# 5VACDC.net
KiCad netlist of a schematic drawn in EAGLE
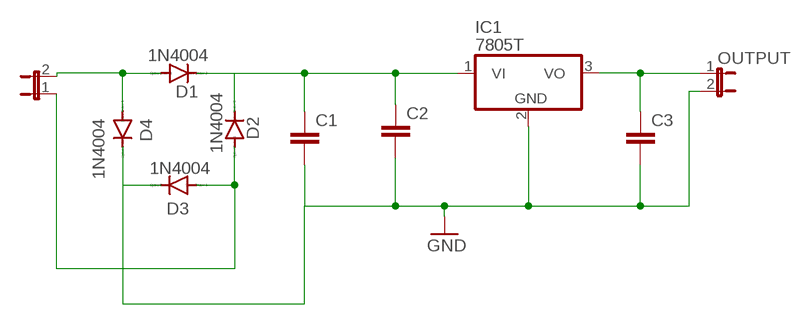
[diagram p0: schematic, sheet 1]

(export (version "E")
  (design (tool "Eeschema 10.0.6"))
  (components
    (comp (ref "C1")
      (value "C2,5-3")
      (footprint "eagle-import:C2.5-3")
      (libsource (lib "eagle-import") (part "C2,5-3"))
    )
    (comp (ref "C2")
      (value "C2,5-3")
      (footprint "eagle-import:C2.5-3")
      (libsource (lib "eagle-import") (part "C2,5-3"))
    )
    (comp (ref "C3")
      (value "C2,5-3")
      (footprint "eagle-import:C2.5-3")
      (libsource (lib "eagle-import") (part "C2,5-3"))
    )
    (comp (ref "D1")
      (value "1N4004")
      (footprint "eagle-import:DO41-10")
      (libsource (lib "eagle-import") (part "1N4004"))
    )
    (comp (ref "D2")
      (value "1N4004")
      (footprint "eagle-import:DO41-10")
      (libsource (lib "eagle-import") (part "1N4004"))
    )
    (comp (ref "D3")
      (value "1N4004")
      (footprint "eagle-import:DO41-10")
      (libsource (lib "eagle-import") (part "1N4004"))
    )
    (comp (ref "D4")
      (value "1N4004")
      (footprint "eagle-import:DO41-10")
      (libsource (lib "eagle-import") (part "1N4004"))
    )
    (comp (ref "IC1")
      (value "7805T")
      (footprint "eagle-import:TO220H")
      (libsource (lib "eagle-import") (part "78T05"))
    )
    (comp (ref "INPUT")
      (value "JP1E")
      (footprint "eagle-import:JP1")
      (libsource (lib "eagle-import") (part "JP1E"))
    )
    (comp (ref "OUTPUT")
      (value "JP1E")
      (footprint "eagle-import:JP1")
      (libsource (lib "eagle-import") (part "JP1E"))
    )
  )
  (nets
    (net (code "1") (name "GND") (class "Default")
      (node (ref "C1") (pin "2") (pinfunction "2_2") (pintype "passive"))
      (node (ref "C2") (pin "2") (pinfunction "2_2") (pintype "passive"))
      (node (ref "C3") (pin "2") (pinfunction "2_2") (pintype "passive"))
      (node (ref "D3") (pin "C") (pinfunction "C_C") (pintype "passive"))
      (node (ref "D4") (pin "C") (pinfunction "C_C") (pintype "passive"))
      (node (ref "IC1") (pin "2") (pinfunction "GND_2") (pintype "passive"))
      (node (ref "OUTPUT") (pin "2") (pinfunction "2_2") (pintype "passive"))
    )
    (net (code "2") (name "Net-(D1-PadA)") (class "Default")
      (node (ref "D1") (pin "A") (pinfunction "A_A") (pintype "passive"))
      (node (ref "D4") (pin "A") (pinfunction "A_A") (pintype "passive"))
      (node (ref "INPUT") (pin "2") (pinfunction "2_2") (pintype "passive"))
    )
    (net (code "3") (name "Net-(D2-PadA)") (class "Default")
      (node (ref "D2") (pin "A") (pinfunction "A_A") (pintype "passive"))
      (node (ref "D3") (pin "A") (pinfunction "A_A") (pintype "passive"))
      (node (ref "INPUT") (pin "1") (pinfunction "1_1") (pintype "passive"))
    )
    (net (code "4") (name "Net-(IC1-VI)") (class "Default")
      (node (ref "C1") (pin "1") (pinfunction "1_1") (pintype "passive"))
      (node (ref "C2") (pin "1") (pinfunction "1_1") (pintype "passive"))
      (node (ref "D1") (pin "C") (pinfunction "C_C") (pintype "passive"))
      (node (ref "D2") (pin "C") (pinfunction "C_C") (pintype "passive"))
      (node (ref "IC1") (pin "1") (pinfunction "VI_1") (pintype "input"))
    )
    (net (code "5") (name "Net-(IC1-VO)") (class "Default")
      (node (ref "C3") (pin "1") (pinfunction "1_1") (pintype "passive"))
      (node (ref "IC1") (pin "3") (pinfunction "VO_3") (pintype "passive"))
      (node (ref "OUTPUT") (pin "1") (pinfunction "1_1") (pintype "passive"))
    )
  )
)
